# sweet_spot_keyboard.net
KiCad netlist of a schematic drawn in EasyEDA
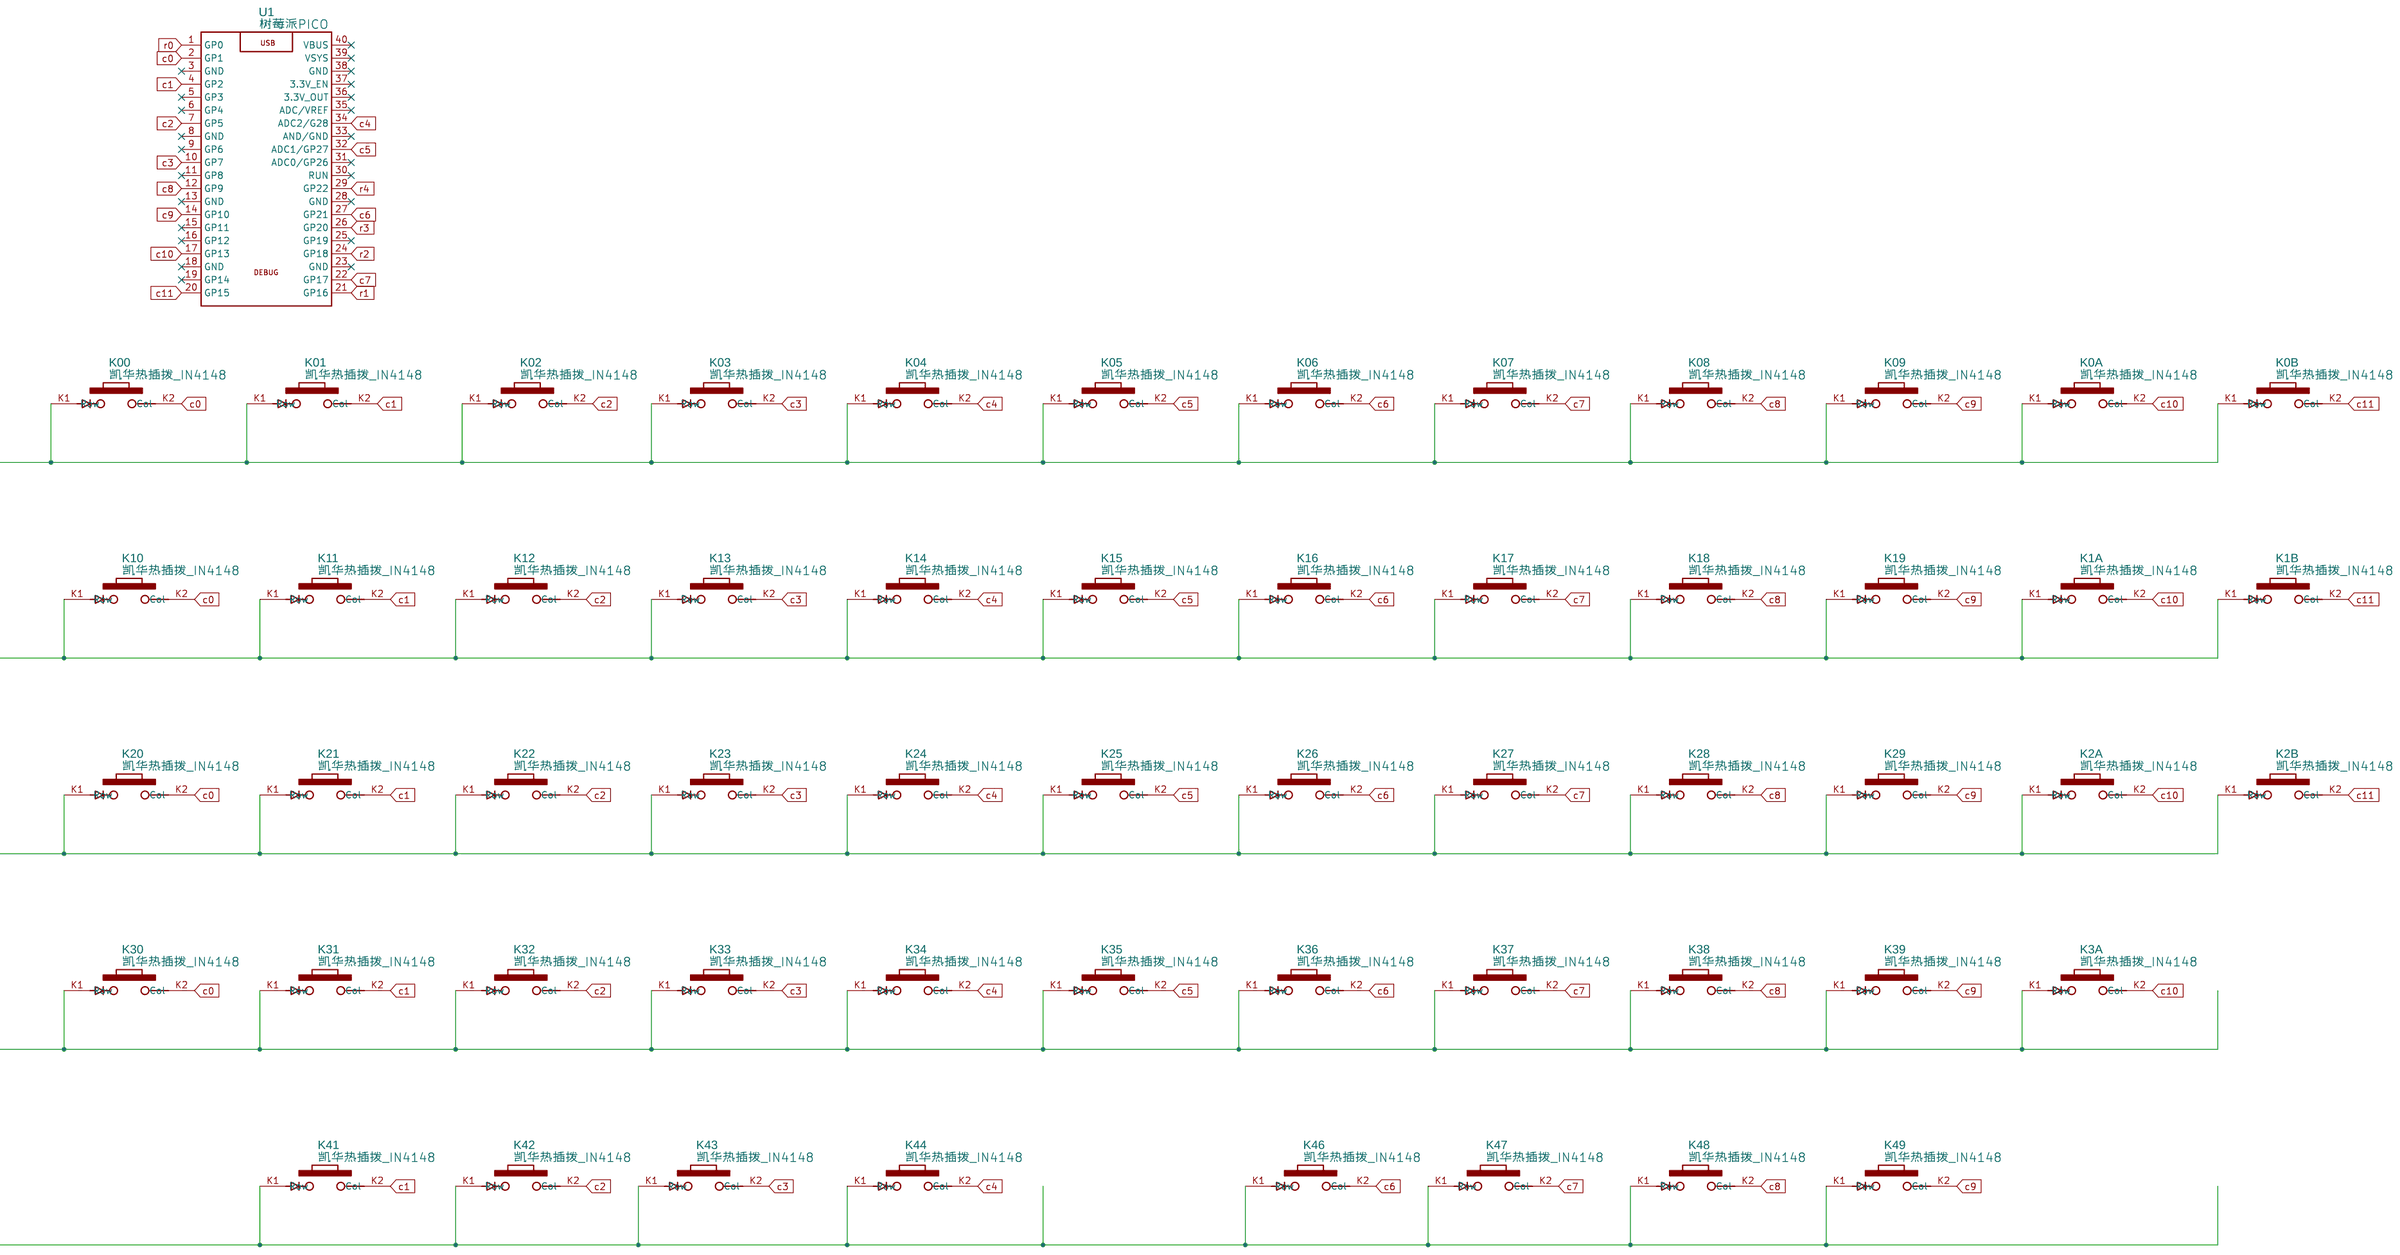
[diagram p0: schematic sheet]

(export (version "E")
  (design (tool "Eeschema 10.0.6"))
  (components
    (comp (ref "K00")
      (value "凯华热插拨_IN4148")
      (fields (field (name "Manufacturer") "Kailh(凯华)"))
      (libsource (lib "") (part "凯华热插拨_IN4148 COPY"))
    )
    (comp (ref "K0A")
      (value "凯华热插拨_IN4148")
      (fields (field (name "Manufacturer") "Kailh(凯华)"))
      (libsource (lib "") (part "凯华热插拨_IN4148 COPY_7"))
    )
    (comp (ref "K0B")
      (value "凯华热插拨_IN4148")
      (fields (field (name "Manufacturer") "Kailh(凯华)"))
      (libsource (lib "") (part "凯华热插拨_IN4148 COPY_3"))
    )
    (comp (ref "K01")
      (value "凯华热插拨_IN4148")
      (fields (field (name "Manufacturer") "Kailh(凯华)"))
      (libsource (lib "") (part "凯华热插拨_IN4148 COPY"))
    )
    (comp (ref "K1A")
      (value "凯华热插拨_IN4148")
      (fields (field (name "Manufacturer") "Kailh(凯华)"))
      (libsource (lib "") (part "凯华热插拨_IN4148 COPY_1"))
    )
    (comp (ref "K1B")
      (value "凯华热插拨_IN4148")
      (fields (field (name "Manufacturer") "Kailh(凯华)"))
      (libsource (lib "") (part "凯华热插拨_IN4148 COPY_5"))
    )
    (comp (ref "K02")
      (value "凯华热插拨_IN4148")
      (fields (field (name "Manufacturer") "Kailh(凯华)"))
      (libsource (lib "") (part "凯华热插拨_IN4148 COPY"))
    )
    (comp (ref "K2A")
      (value "凯华热插拨_IN4148")
      (fields (field (name "Manufacturer") "Kailh(凯华)"))
      (libsource (lib "") (part "凯华热插拨_IN4148 COPY_4"))
    )
    (comp (ref "K2B")
      (value "凯华热插拨_IN4148")
      (fields (field (name "Manufacturer") "Kailh(凯华)"))
      (libsource (lib "") (part "凯华热插拨_IN4148 COPY_6"))
    )
    (comp (ref "K03")
      (value "凯华热插拨_IN4148")
      (fields (field (name "Manufacturer") "Kailh(凯华)"))
      (libsource (lib "") (part "凯华热插拨_IN4148 COPY"))
    )
    (comp (ref "K3A")
      (value "凯华热插拨_IN4148")
      (fields (field (name "Manufacturer") "Kailh(凯华)"))
      (libsource (lib "") (part "凯华热插拨_IN4148 COPY_2"))
    )
    (comp (ref "K04")
      (value "凯华热插拨_IN4148")
      (fields (field (name "Manufacturer") "Kailh(凯华)"))
      (libsource (lib "") (part "凯华热插拨_IN4148 COPY"))
    )
    (comp (ref "K05")
      (value "凯华热插拨_IN4148")
      (fields (field (name "Manufacturer") "Kailh(凯华)"))
      (libsource (lib "") (part "凯华热插拨_IN4148 COPY"))
    )
    (comp (ref "K06")
      (value "凯华热插拨_IN4148")
      (fields (field (name "Manufacturer") "Kailh(凯华)"))
      (libsource (lib "") (part "凯华热插拨_IN4148 COPY"))
    )
    (comp (ref "K07")
      (value "凯华热插拨_IN4148")
      (fields (field (name "Manufacturer") "Kailh(凯华)"))
      (libsource (lib "") (part "凯华热插拨_IN4148 COPY"))
    )
    (comp (ref "K08")
      (value "凯华热插拨_IN4148")
      (fields (field (name "Manufacturer") "Kailh(凯华)"))
      (libsource (lib "") (part "凯华热插拨_IN4148 COPY"))
    )
    (comp (ref "K09")
      (value "凯华热插拨_IN4148")
      (fields (field (name "Manufacturer") "Kailh(凯华)"))
      (libsource (lib "") (part "凯华热插拨_IN4148 COPY"))
    )
    (comp (ref "K10")
      (value "凯华热插拨_IN4148")
      (fields (field (name "Manufacturer") "Kailh(凯华)"))
      (libsource (lib "") (part "凯华热插拨_IN4148 COPY"))
    )
    (comp (ref "K11")
      (value "凯华热插拨_IN4148")
      (fields (field (name "Manufacturer") "Kailh(凯华)"))
      (libsource (lib "") (part "凯华热插拨_IN4148 COPY"))
    )
    (comp (ref "K12")
      (value "凯华热插拨_IN4148")
      (fields (field (name "Manufacturer") "Kailh(凯华)"))
      (libsource (lib "") (part "凯华热插拨_IN4148 COPY"))
    )
    (comp (ref "K13")
      (value "凯华热插拨_IN4148")
      (fields (field (name "Manufacturer") "Kailh(凯华)"))
      (libsource (lib "") (part "凯华热插拨_IN4148 COPY"))
    )
    (comp (ref "K14")
      (value "凯华热插拨_IN4148")
      (fields (field (name "Manufacturer") "Kailh(凯华)"))
      (libsource (lib "") (part "凯华热插拨_IN4148 COPY"))
    )
    (comp (ref "K15")
      (value "凯华热插拨_IN4148")
      (fields (field (name "Manufacturer") "Kailh(凯华)"))
      (libsource (lib "") (part "凯华热插拨_IN4148 COPY"))
    )
    (comp (ref "K16")
      (value "凯华热插拨_IN4148")
      (fields (field (name "Manufacturer") "Kailh(凯华)"))
      (libsource (lib "") (part "凯华热插拨_IN4148 COPY"))
    )
    (comp (ref "K17")
      (value "凯华热插拨_IN4148")
      (fields (field (name "Manufacturer") "Kailh(凯华)"))
      (libsource (lib "") (part "凯华热插拨_IN4148 COPY"))
    )
    (comp (ref "K18")
      (value "凯华热插拨_IN4148")
      (fields (field (name "Manufacturer") "Kailh(凯华)"))
      (libsource (lib "") (part "凯华热插拨_IN4148 COPY"))
    )
    (comp (ref "K19")
      (value "凯华热插拨_IN4148")
      (fields (field (name "Manufacturer") "Kailh(凯华)"))
      (libsource (lib "") (part "凯华热插拨_IN4148 COPY"))
    )
    (comp (ref "K20")
      (value "凯华热插拨_IN4148")
      (fields (field (name "Manufacturer") "Kailh(凯华)"))
      (libsource (lib "") (part "凯华热插拨_IN4148 COPY"))
    )
    (comp (ref "K21")
      (value "凯华热插拨_IN4148")
      (fields (field (name "Manufacturer") "Kailh(凯华)"))
      (libsource (lib "") (part "凯华热插拨_IN4148 COPY"))
    )
    (comp (ref "K22")
      (value "凯华热插拨_IN4148")
      (fields (field (name "Manufacturer") "Kailh(凯华)"))
      (libsource (lib "") (part "凯华热插拨_IN4148 COPY"))
    )
    (comp (ref "K23")
      (value "凯华热插拨_IN4148")
      (fields (field (name "Manufacturer") "Kailh(凯华)"))
      (libsource (lib "") (part "凯华热插拨_IN4148 COPY"))
    )
    (comp (ref "K24")
      (value "凯华热插拨_IN4148")
      (fields (field (name "Manufacturer") "Kailh(凯华)"))
      (libsource (lib "") (part "凯华热插拨_IN4148 COPY"))
    )
    (comp (ref "K25")
      (value "凯华热插拨_IN4148")
      (fields (field (name "Manufacturer") "Kailh(凯华)"))
      (libsource (lib "") (part "凯华热插拨_IN4148 COPY"))
    )
    (comp (ref "K26")
      (value "凯华热插拨_IN4148")
      (fields (field (name "Manufacturer") "Kailh(凯华)"))
      (libsource (lib "") (part "凯华热插拨_IN4148 COPY"))
    )
    (comp (ref "K27")
      (value "凯华热插拨_IN4148")
      (fields (field (name "Manufacturer") "Kailh(凯华)"))
      (libsource (lib "") (part "凯华热插拨_IN4148 COPY"))
    )
    (comp (ref "K28")
      (value "凯华热插拨_IN4148")
      (fields (field (name "Manufacturer") "Kailh(凯华)"))
      (libsource (lib "") (part "凯华热插拨_IN4148 COPY"))
    )
    (comp (ref "K29")
      (value "凯华热插拨_IN4148")
      (fields (field (name "Manufacturer") "Kailh(凯华)"))
      (libsource (lib "") (part "凯华热插拨_IN4148 COPY"))
    )
    (comp (ref "K30")
      (value "凯华热插拨_IN4148")
      (fields (field (name "Manufacturer") "Kailh(凯华)"))
      (libsource (lib "") (part "凯华热插拨_IN4148 COPY"))
    )
    (comp (ref "K31")
      (value "凯华热插拨_IN4148")
      (fields (field (name "Manufacturer") "Kailh(凯华)"))
      (libsource (lib "") (part "凯华热插拨_IN4148 COPY"))
    )
    (comp (ref "K32")
      (value "凯华热插拨_IN4148")
      (fields (field (name "Manufacturer") "Kailh(凯华)"))
      (libsource (lib "") (part "凯华热插拨_IN4148 COPY"))
    )
    (comp (ref "K33")
      (value "凯华热插拨_IN4148")
      (fields (field (name "Manufacturer") "Kailh(凯华)"))
      (libsource (lib "") (part "凯华热插拨_IN4148 COPY"))
    )
    (comp (ref "K34")
      (value "凯华热插拨_IN4148")
      (fields (field (name "Manufacturer") "Kailh(凯华)"))
      (libsource (lib "") (part "凯华热插拨_IN4148 COPY"))
    )
    (comp (ref "K35")
      (value "凯华热插拨_IN4148")
      (fields (field (name "Manufacturer") "Kailh(凯华)"))
      (libsource (lib "") (part "凯华热插拨_IN4148 COPY"))
    )
    (comp (ref "K36")
      (value "凯华热插拨_IN4148")
      (fields (field (name "Manufacturer") "Kailh(凯华)"))
      (libsource (lib "") (part "凯华热插拨_IN4148 COPY"))
    )
    (comp (ref "K37")
      (value "凯华热插拨_IN4148")
      (fields (field (name "Manufacturer") "Kailh(凯华)"))
      (libsource (lib "") (part "凯华热插拨_IN4148 COPY"))
    )
    (comp (ref "K38")
      (value "凯华热插拨_IN4148")
      (fields (field (name "Manufacturer") "Kailh(凯华)"))
      (libsource (lib "") (part "凯华热插拨_IN4148 COPY"))
    )
    (comp (ref "K39")
      (value "凯华热插拨_IN4148")
      (fields (field (name "Manufacturer") "Kailh(凯华)"))
      (libsource (lib "") (part "凯华热插拨_IN4148 COPY"))
    )
    (comp (ref "K41")
      (value "凯华热插拨_IN4148")
      (fields (field (name "Manufacturer") "Kailh(凯华)"))
      (libsource (lib "") (part "凯华热插拨_IN4148 COPY"))
    )
    (comp (ref "K42")
      (value "凯华热插拨_IN4148")
      (fields (field (name "Manufacturer") "Kailh(凯华)"))
      (libsource (lib "") (part "凯华热插拨_IN4148 COPY"))
    )
    (comp (ref "K43")
      (value "凯华热插拨_IN4148")
      (fields (field (name "Manufacturer") "Kailh(凯华)"))
      (libsource (lib "") (part "凯华热插拨_IN4148 COPY"))
    )
    (comp (ref "K44")
      (value "凯华热插拨_IN4148")
      (fields (field (name "Manufacturer") "Kailh(凯华)"))
      (libsource (lib "") (part "凯华热插拨_IN4148 COPY"))
    )
    (comp (ref "K46")
      (value "凯华热插拨_IN4148")
      (fields (field (name "Manufacturer") "Kailh(凯华)"))
      (libsource (lib "") (part "凯华热插拨_IN4148 COPY"))
    )
    (comp (ref "K47")
      (value "凯华热插拨_IN4148")
      (fields (field (name "Manufacturer") "Kailh(凯华)"))
      (libsource (lib "") (part "凯华热插拨_IN4148 COPY"))
    )
    (comp (ref "K48")
      (value "凯华热插拨_IN4148")
      (fields (field (name "Manufacturer") "Kailh(凯华)"))
      (libsource (lib "") (part "凯华热插拨_IN4148 COPY"))
    )
    (comp (ref "K49")
      (value "凯华热插拨_IN4148")
      (fields (field (name "Manufacturer") "Kailh(凯华)"))
      (libsource (lib "") (part "凯华热插拨_IN4148 COPY"))
    )
    (comp (ref "U1") (value "树莓派PICO") (libsource (lib "") (part "树莓派PICO")))
  )
  (nets
    (net (code "1") (name "c0") (class "Default")
      (node (ref "K00") (pin "K2") (pinfunction "Col_K2") (pintype "output"))
      (node (ref "K10") (pin "K2") (pinfunction "Col_K2") (pintype "output"))
      (node (ref "K20") (pin "K2") (pinfunction "Col_K2") (pintype "output"))
      (node (ref "K30") (pin "K2") (pinfunction "Col_K2") (pintype "output"))
      (node (ref "U1") (pin "2") (pinfunction "GP1_2") (pintype "unspecified"))
    )
    (net (code "2") (name "c1") (class "Default")
      (node (ref "K01") (pin "K2") (pinfunction "Col_K2") (pintype "output"))
      (node (ref "K11") (pin "K2") (pinfunction "Col_K2") (pintype "output"))
      (node (ref "K21") (pin "K2") (pinfunction "Col_K2") (pintype "output"))
      (node (ref "K31") (pin "K2") (pinfunction "Col_K2") (pintype "output"))
      (node (ref "K41") (pin "K2") (pinfunction "Col_K2") (pintype "output"))
      (node (ref "U1") (pin "4") (pinfunction "GP2_4") (pintype "unspecified"))
    )
    (net (code "3") (name "c2") (class "Default")
      (node (ref "K02") (pin "K2") (pinfunction "Col_K2") (pintype "output"))
      (node (ref "K12") (pin "K2") (pinfunction "Col_K2") (pintype "output"))
      (node (ref "K22") (pin "K2") (pinfunction "Col_K2") (pintype "output"))
      (node (ref "K32") (pin "K2") (pinfunction "Col_K2") (pintype "output"))
      (node (ref "K42") (pin "K2") (pinfunction "Col_K2") (pintype "output"))
      (node (ref "U1") (pin "7") (pinfunction "GP5_7") (pintype "unspecified"))
    )
    (net (code "4") (name "c3") (class "Default")
      (node (ref "K03") (pin "K2") (pinfunction "Col_K2") (pintype "output"))
      (node (ref "K13") (pin "K2") (pinfunction "Col_K2") (pintype "output"))
      (node (ref "K23") (pin "K2") (pinfunction "Col_K2") (pintype "output"))
      (node (ref "K33") (pin "K2") (pinfunction "Col_K2") (pintype "output"))
      (node (ref "K43") (pin "K2") (pinfunction "Col_K2") (pintype "output"))
      (node (ref "U1") (pin "10") (pinfunction "GP7_10") (pintype "unspecified"))
    )
    (net (code "5") (name "c4") (class "Default")
      (node (ref "K04") (pin "K2") (pinfunction "Col_K2") (pintype "output"))
      (node (ref "K14") (pin "K2") (pinfunction "Col_K2") (pintype "output"))
      (node (ref "K24") (pin "K2") (pinfunction "Col_K2") (pintype "output"))
      (node (ref "K34") (pin "K2") (pinfunction "Col_K2") (pintype "output"))
      (node (ref "K44") (pin "K2") (pinfunction "Col_K2") (pintype "output"))
      (node (ref "U1") (pin "34") (pinfunction "ADC2/G28_34") (pintype "unspecified"))
    )
    (net (code "6") (name "c5") (class "Default")
      (node (ref "K05") (pin "K2") (pinfunction "Col_K2") (pintype "output"))
      (node (ref "K15") (pin "K2") (pinfunction "Col_K2") (pintype "output"))
      (node (ref "K25") (pin "K2") (pinfunction "Col_K2") (pintype "output"))
      (node (ref "K35") (pin "K2") (pinfunction "Col_K2") (pintype "output"))
      (node (ref "U1") (pin "32") (pinfunction "ADC1/GP27_32") (pintype "unspecified"))
    )
    (net (code "7") (name "c6") (class "Default")
      (node (ref "K06") (pin "K2") (pinfunction "Col_K2") (pintype "output"))
      (node (ref "K16") (pin "K2") (pinfunction "Col_K2") (pintype "output"))
      (node (ref "K26") (pin "K2") (pinfunction "Col_K2") (pintype "output"))
      (node (ref "K36") (pin "K2") (pinfunction "Col_K2") (pintype "output"))
      (node (ref "K46") (pin "K2") (pinfunction "Col_K2") (pintype "output"))
      (node (ref "U1") (pin "27") (pinfunction "GP21_27") (pintype "unspecified"))
    )
    (net (code "8") (name "c7") (class "Default")
      (node (ref "K07") (pin "K2") (pinfunction "Col_K2") (pintype "output"))
      (node (ref "K17") (pin "K2") (pinfunction "Col_K2") (pintype "output"))
      (node (ref "K27") (pin "K2") (pinfunction "Col_K2") (pintype "output"))
      (node (ref "K37") (pin "K2") (pinfunction "Col_K2") (pintype "output"))
      (node (ref "K47") (pin "K2") (pinfunction "Col_K2") (pintype "output"))
      (node (ref "U1") (pin "22") (pinfunction "GP17_22") (pintype "unspecified"))
    )
    (net (code "9") (name "c8") (class "Default")
      (node (ref "K08") (pin "K2") (pinfunction "Col_K2") (pintype "output"))
      (node (ref "K18") (pin "K2") (pinfunction "Col_K2") (pintype "output"))
      (node (ref "K28") (pin "K2") (pinfunction "Col_K2") (pintype "output"))
      (node (ref "K38") (pin "K2") (pinfunction "Col_K2") (pintype "output"))
      (node (ref "K48") (pin "K2") (pinfunction "Col_K2") (pintype "output"))
      (node (ref "U1") (pin "12") (pinfunction "GP9_12") (pintype "unspecified"))
    )
    (net (code "10") (name "c9") (class "Default")
      (node (ref "K09") (pin "K2") (pinfunction "Col_K2") (pintype "output"))
      (node (ref "K19") (pin "K2") (pinfunction "Col_K2") (pintype "output"))
      (node (ref "K29") (pin "K2") (pinfunction "Col_K2") (pintype "output"))
      (node (ref "K39") (pin "K2") (pinfunction "Col_K2") (pintype "output"))
      (node (ref "K49") (pin "K2") (pinfunction "Col_K2") (pintype "output"))
      (node (ref "U1") (pin "14") (pinfunction "GP10_14") (pintype "unspecified"))
    )
    (net (code "11") (name "c10") (class "Default")
      (node (ref "K0A") (pin "K2") (pinfunction "Col_K2") (pintype "output"))
      (node (ref "K1A") (pin "K2") (pinfunction "Col_K2") (pintype "output"))
      (node (ref "K2A") (pin "K2") (pinfunction "Col_K2") (pintype "output"))
      (node (ref "K3A") (pin "K2") (pinfunction "Col_K2") (pintype "output"))
      (node (ref "U1") (pin "17") (pinfunction "GP13_17") (pintype "unspecified"))
    )
    (net (code "12") (name "c11") (class "Default")
      (node (ref "K0B") (pin "K2") (pinfunction "Col_K2") (pintype "output"))
      (node (ref "K1B") (pin "K2") (pinfunction "Col_K2") (pintype "output"))
      (node (ref "K2B") (pin "K2") (pinfunction "Col_K2") (pintype "output"))
      (node (ref "U1") (pin "20") (pinfunction "GP15_20") (pintype "unspecified"))
    )
    (net (code "13") (name "r0") (class "Default")
      (node (ref "K00") (pin "K1") (pinfunction "Row_K1") (pintype "input"))
      (node (ref "K01") (pin "K1") (pinfunction "Row_K1") (pintype "input"))
      (node (ref "K02") (pin "K1") (pinfunction "Row_K1") (pintype "input"))
      (node (ref "K03") (pin "K1") (pinfunction "Row_K1") (pintype "input"))
      (node (ref "K04") (pin "K1") (pinfunction "Row_K1") (pintype "input"))
      (node (ref "K05") (pin "K1") (pinfunction "Row_K1") (pintype "input"))
      (node (ref "K06") (pin "K1") (pinfunction "Row_K1") (pintype "input"))
      (node (ref "K07") (pin "K1") (pinfunction "Row_K1") (pintype "input"))
      (node (ref "K08") (pin "K1") (pinfunction "Row_K1") (pintype "input"))
      (node (ref "K09") (pin "K1") (pinfunction "Row_K1") (pintype "input"))
      (node (ref "K0A") (pin "K1") (pinfunction "Row_K1") (pintype "input"))
      (node (ref "K0B") (pin "K1") (pinfunction "Row_K1") (pintype "input"))
      (node (ref "U1") (pin "1") (pinfunction "GP0_1") (pintype "unspecified"))
    )
    (net (code "14") (name "r1") (class "Default")
      (node (ref "K10") (pin "K1") (pinfunction "Row_K1") (pintype "input"))
      (node (ref "K11") (pin "K1") (pinfunction "Row_K1") (pintype "input"))
      (node (ref "K12") (pin "K1") (pinfunction "Row_K1") (pintype "input"))
      (node (ref "K13") (pin "K1") (pinfunction "Row_K1") (pintype "input"))
      (node (ref "K14") (pin "K1") (pinfunction "Row_K1") (pintype "input"))
      (node (ref "K15") (pin "K1") (pinfunction "Row_K1") (pintype "input"))
      (node (ref "K16") (pin "K1") (pinfunction "Row_K1") (pintype "input"))
      (node (ref "K17") (pin "K1") (pinfunction "Row_K1") (pintype "input"))
      (node (ref "K18") (pin "K1") (pinfunction "Row_K1") (pintype "input"))
      (node (ref "K19") (pin "K1") (pinfunction "Row_K1") (pintype "input"))
      (node (ref "K1A") (pin "K1") (pinfunction "Row_K1") (pintype "input"))
      (node (ref "K1B") (pin "K1") (pinfunction "Row_K1") (pintype "input"))
      (node (ref "U1") (pin "21") (pinfunction "GP16_21") (pintype "unspecified"))
    )
    (net (code "15") (name "r2") (class "Default")
      (node (ref "K20") (pin "K1") (pinfunction "Row_K1") (pintype "input"))
      (node (ref "K21") (pin "K1") (pinfunction "Row_K1") (pintype "input"))
      (node (ref "K22") (pin "K1") (pinfunction "Row_K1") (pintype "input"))
      (node (ref "K23") (pin "K1") (pinfunction "Row_K1") (pintype "input"))
      (node (ref "K24") (pin "K1") (pinfunction "Row_K1") (pintype "input"))
      (node (ref "K25") (pin "K1") (pinfunction "Row_K1") (pintype "input"))
      (node (ref "K26") (pin "K1") (pinfunction "Row_K1") (pintype "input"))
      (node (ref "K27") (pin "K1") (pinfunction "Row_K1") (pintype "input"))
      (node (ref "K28") (pin "K1") (pinfunction "Row_K1") (pintype "input"))
      (node (ref "K29") (pin "K1") (pinfunction "Row_K1") (pintype "input"))
      (node (ref "K2A") (pin "K1") (pinfunction "Row_K1") (pintype "input"))
      (node (ref "K2B") (pin "K1") (pinfunction "Row_K1") (pintype "input"))
      (node (ref "U1") (pin "24") (pinfunction "GP18_24") (pintype "unspecified"))
    )
    (net (code "16") (name "r3") (class "Default")
      (node (ref "K30") (pin "K1") (pinfunction "Row_K1") (pintype "input"))
      (node (ref "K31") (pin "K1") (pinfunction "Row_K1") (pintype "input"))
      (node (ref "K32") (pin "K1") (pinfunction "Row_K1") (pintype "input"))
      (node (ref "K33") (pin "K1") (pinfunction "Row_K1") (pintype "input"))
      (node (ref "K34") (pin "K1") (pinfunction "Row_K1") (pintype "input"))
      (node (ref "K35") (pin "K1") (pinfunction "Row_K1") (pintype "input"))
      (node (ref "K36") (pin "K1") (pinfunction "Row_K1") (pintype "input"))
      (node (ref "K37") (pin "K1") (pinfunction "Row_K1") (pintype "input"))
      (node (ref "K38") (pin "K1") (pinfunction "Row_K1") (pintype "input"))
      (node (ref "K39") (pin "K1") (pinfunction "Row_K1") (pintype "input"))
      (node (ref "K3A") (pin "K1") (pinfunction "Row_K1") (pintype "input"))
      (node (ref "U1") (pin "26") (pinfunction "GP20_26") (pintype "unspecified"))
    )
    (net (code "17") (name "r4") (class "Default")
      (node (ref "K41") (pin "K1") (pinfunction "Row_K1") (pintype "input"))
      (node (ref "K42") (pin "K1") (pinfunction "Row_K1") (pintype "input"))
      (node (ref "K43") (pin "K1") (pinfunction "Row_K1") (pintype "input"))
      (node (ref "K44") (pin "K1") (pinfunction "Row_K1") (pintype "input"))
      (node (ref "K46") (pin "K1") (pinfunction "Row_K1") (pintype "input"))
      (node (ref "K47") (pin "K1") (pinfunction "Row_K1") (pintype "input"))
      (node (ref "K48") (pin "K1") (pinfunction "Row_K1") (pintype "input"))
      (node (ref "K49") (pin "K1") (pinfunction "Row_K1") (pintype "input"))
      (node (ref "U1") (pin "29") (pinfunction "GP22_29") (pintype "unspecified"))
    )
    (net (code "18") (name "unconnected-(U1-3.3V_EN-Pad37)") (class "Default")
      (node (ref "U1") (pin "37") (pinfunction "3.3V_EN_37") (pintype "unspecified+no_connect"))
    )
    (net (code "19") (name "unconnected-(U1-3.3V_OUT-Pad36)") (class "Default")
      (node (ref "U1") (pin "36") (pinfunction "3.3V_OUT_36") (pintype "unspecified+no_connect"))
    )
    (net (code "20") (name "unconnected-(U1-ADC0{slash}GP26-Pad31)") (class "Default")
      (node (ref "U1") (pin "31") (pinfunction "ADC0/GP26_31") (pintype "unspecified+no_connect"))
    )
    (net (code "21") (name "unconnected-(U1-ADC{slash}VREF-Pad35)") (class "Default")
      (node (ref "U1") (pin "35") (pinfunction "ADC/VREF_35") (pintype "unspecified+no_connect"))
    )
    (net (code "22") (name "unconnected-(U1-AND{slash}GND-Pad33)") (class "Default")
      (node (ref "U1") (pin "33") (pinfunction "AND/GND_33") (pintype "unspecified+no_connect"))
    )
    (net (code "23") (name "unconnected-(U1-GND-Pad3)") (class "Default")
      (node (ref "U1") (pin "3") (pinfunction "GND_3") (pintype "unspecified+no_connect"))
    )
    (net (code "24") (name "unconnected-(U1-GND-Pad8)") (class "Default")
      (node (ref "U1") (pin "8") (pinfunction "GND_8") (pintype "unspecified+no_connect"))
    )
    (net (code "25") (name "unconnected-(U1-GND-Pad13)") (class "Default")
      (node (ref "U1") (pin "13") (pinfunction "GND_13") (pintype "unspecified+no_connect"))
    )
    (net (code "26") (name "unconnected-(U1-GND-Pad18)") (class "Default")
      (node (ref "U1") (pin "18") (pinfunction "GND_18") (pintype "unspecified+no_connect"))
    )
    (net (code "27") (name "unconnected-(U1-GND-Pad23)") (class "Default")
      (node (ref "U1") (pin "23") (pinfunction "GND_23") (pintype "unspecified+no_connect"))
    )
    (net (code "28") (name "unconnected-(U1-GND-Pad28)") (class "Default")
      (node (ref "U1") (pin "28") (pinfunction "GND_28") (pintype "unspecified+no_connect"))
    )
    (net (code "29") (name "unconnected-(U1-GND-Pad38)") (class "Default")
      (node (ref "U1") (pin "38") (pinfunction "GND_38") (pintype "unspecified+no_connect"))
    )
    (net (code "30") (name "unconnected-(U1-GP3-Pad5)") (class "Default")
      (node (ref "U1") (pin "5") (pinfunction "GP3_5") (pintype "unspecified+no_connect"))
    )
    (net (code "31") (name "unconnected-(U1-GP4-Pad6)") (class "Default")
      (node (ref "U1") (pin "6") (pinfunction "GP4_6") (pintype "unspecified+no_connect"))
    )
    (net (code "32") (name "unconnected-(U1-GP6-Pad9)") (class "Default")
      (node (ref "U1") (pin "9") (pinfunction "GP6_9") (pintype "unspecified+no_connect"))
    )
    (net (code "33") (name "unconnected-(U1-GP8-Pad11)") (class "Default")
      (node (ref "U1") (pin "11") (pinfunction "GP8_11") (pintype "unspecified+no_connect"))
    )
    (net (code "34") (name "unconnected-(U1-GP11-Pad15)") (class "Default")
      (node (ref "U1") (pin "15") (pinfunction "GP11_15") (pintype "unspecified+no_connect"))
    )
    (net (code "35") (name "unconnected-(U1-GP12-Pad16)") (class "Default")
      (node (ref "U1") (pin "16") (pinfunction "GP12_16") (pintype "unspecified+no_connect"))
    )
    (net (code "36") (name "unconnected-(U1-GP14-Pad19)") (class "Default")
      (node (ref "U1") (pin "19") (pinfunction "GP14_19") (pintype "unspecified+no_connect"))
    )
    (net (code "37") (name "unconnected-(U1-GP19-Pad25)") (class "Default")
      (node (ref "U1") (pin "25") (pinfunction "GP19_25") (pintype "unspecified+no_connect"))
    )
    (net (code "38") (name "unconnected-(U1-RUN-Pad30)") (class "Default")
      (node (ref "U1") (pin "30") (pinfunction "RUN_30") (pintype "unspecified+no_connect"))
    )
    (net (code "39") (name "unconnected-(U1-VBUS-Pad40)") (class "Default")
      (node (ref "U1") (pin "40") (pinfunction "VBUS_40") (pintype "unspecified+no_connect"))
    )
    (net (code "40") (name "unconnected-(U1-VSYS-Pad39)") (class "Default")
      (node (ref "U1") (pin "39") (pinfunction "VSYS_39") (pintype "unspecified+no_connect"))
    )
  )
)
